# Display_PCB_Rev_1.net
KiCad netlist of a schematic drawn in EAGLE
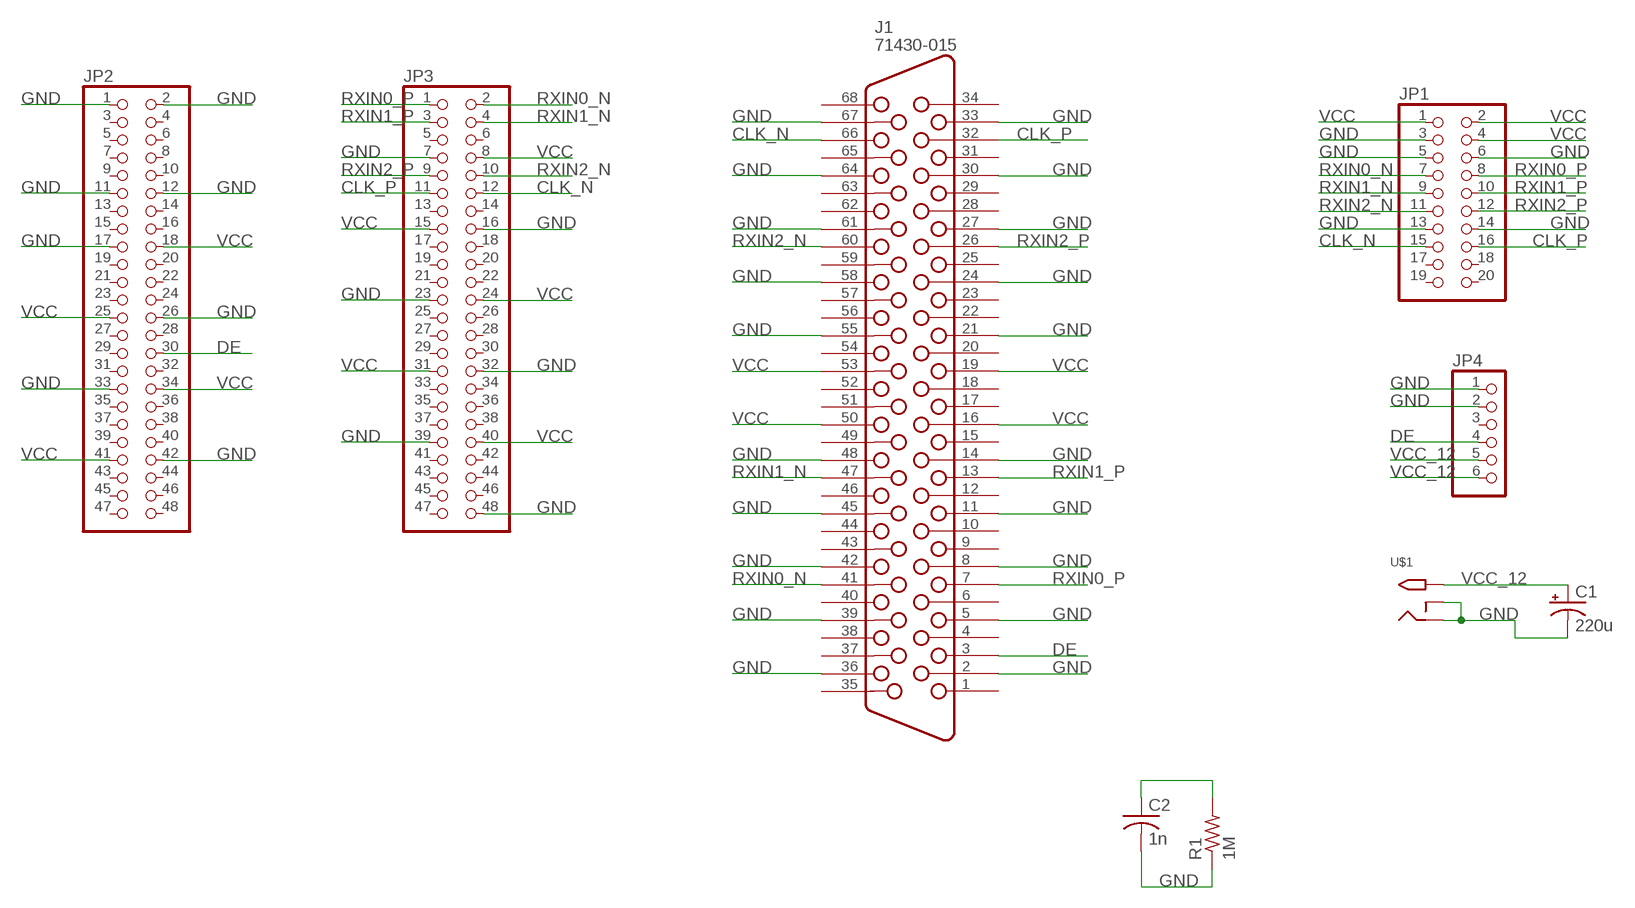
[diagram p0: schematic, sheet 1]

(export (version "E")
  (design (tool "Eeschema 10.0.6"))
  (components
    (comp (ref "C1")
      (value "220u")
      (footprint "eagle-import:E5-8,5")
      (libsource (lib "eagle-import") (part "CPOL-USE5-8.5"))
    )
    (comp (ref "C2")
      (value "1n")
      (footprint "eagle-import:C0805")
      (libsource (lib "eagle-import") (part "C-USC0805"))
    )
    (comp (ref "J1")
      (value "71430-015")
      (footprint "eagle-import:71430-015")
      (libsource (lib "eagle-import") (part "71430-015"))
    )
    (comp (ref "JP1")
      (value "PINHD-2X10M")
      (footprint "eagle-import:2X10M")
      (libsource (lib "eagle-import") (part "PINHD-2X10M"))
    )
    (comp (ref "JP2")
      (value "PINHD-2X24")
      (footprint "eagle-import:2X24")
      (libsource (lib "eagle-import") (part "PINHD-2X24"))
    )
    (comp (ref "JP3")
      (value "PINHD-2X24")
      (footprint "eagle-import:2X24")
      (libsource (lib "eagle-import") (part "PINHD-2X24"))
    )
    (comp (ref "JP4")
      (value "PINHD-1X6M")
      (footprint "eagle-import:1X06M")
      (libsource (lib "eagle-import") (part "PINHD-1X6M"))
    )
    (comp (ref "R1")
      (value "1M")
      (footprint "eagle-import:R0805W")
      (libsource (lib "eagle-import") (part "R-US_R0805W"))
    )
    (comp (ref "U$1")
      (value "2.1MMJACKTHM")
      (footprint "eagle-import:PJ-102A")
      (libsource (lib "eagle-import") (part "2.1MMJACKTHM"))
    )
  )
  (nets
    (net (code "1") (name "/CLK_N") (class "Default")
      (node (ref "J1") (pin "66") (pinfunction "66_66") (pintype "bidirectional"))
      (node (ref "JP1") (pin "15") (pinfunction "15_15") (pintype "passive"))
      (node (ref "JP3") (pin "12") (pinfunction "12_12") (pintype "passive"))
    )
    (net (code "2") (name "/CLK_P") (class "Default")
      (node (ref "J1") (pin "32") (pinfunction "32_32") (pintype "bidirectional"))
      (node (ref "JP1") (pin "16") (pinfunction "16_16") (pintype "passive"))
      (node (ref "JP3") (pin "11") (pinfunction "11_11") (pintype "passive"))
    )
    (net (code "3") (name "/DE") (class "Default")
      (node (ref "J1") (pin "3") (pinfunction "3_3") (pintype "bidirectional"))
      (node (ref "JP2") (pin "30") (pinfunction "30_30") (pintype "passive"))
      (node (ref "JP4") (pin "4") (pinfunction "4_4") (pintype "passive"))
    )
    (net (code "4") (name "/GND") (class "Default")
      (node (ref "C1") (pin "-") (pinfunction "-_-") (pintype "passive"))
      (node (ref "C2") (pin "2") (pinfunction "2_2") (pintype "passive"))
      (node (ref "J1") (pin "11") (pinfunction "11_11") (pintype "bidirectional"))
      (node (ref "J1") (pin "14") (pinfunction "14_14") (pintype "bidirectional"))
      (node (ref "J1") (pin "2") (pinfunction "2_2") (pintype "bidirectional"))
      (node (ref "J1") (pin "21") (pinfunction "21_21") (pintype "bidirectional"))
      (node (ref "J1") (pin "24") (pinfunction "24_24") (pintype "bidirectional"))
      (node (ref "J1") (pin "27") (pinfunction "27_27") (pintype "bidirectional"))
      (node (ref "J1") (pin "30") (pinfunction "30_30") (pintype "bidirectional"))
      (node (ref "J1") (pin "33") (pinfunction "33_33") (pintype "bidirectional"))
      (node (ref "J1") (pin "36") (pinfunction "36_36") (pintype "bidirectional"))
      (node (ref "J1") (pin "39") (pinfunction "39_39") (pintype "bidirectional"))
      (node (ref "J1") (pin "42") (pinfunction "42_42") (pintype "bidirectional"))
      (node (ref "J1") (pin "45") (pinfunction "45_45") (pintype "bidirectional"))
      (node (ref "J1") (pin "48") (pinfunction "48_48") (pintype "bidirectional"))
      (node (ref "J1") (pin "5") (pinfunction "5_5") (pintype "bidirectional"))
      (node (ref "J1") (pin "55") (pinfunction "55_55") (pintype "bidirectional"))
      (node (ref "J1") (pin "58") (pinfunction "58_58") (pintype "bidirectional"))
      (node (ref "J1") (pin "61") (pinfunction "61_61") (pintype "bidirectional"))
      (node (ref "J1") (pin "64") (pinfunction "64_64") (pintype "bidirectional"))
      (node (ref "J1") (pin "67") (pinfunction "67_67") (pintype "bidirectional"))
      (node (ref "J1") (pin "8") (pinfunction "8_8") (pintype "bidirectional"))
      (node (ref "JP1") (pin "13") (pinfunction "13_13") (pintype "passive"))
      (node (ref "JP1") (pin "14") (pinfunction "14_14") (pintype "passive"))
      (node (ref "JP1") (pin "3") (pinfunction "3_3") (pintype "passive"))
      (node (ref "JP1") (pin "5") (pinfunction "5_5") (pintype "passive"))
      (node (ref "JP1") (pin "6") (pinfunction "6_6") (pintype "passive"))
      (node (ref "JP2") (pin "1") (pinfunction "1_1") (pintype "passive"))
      (node (ref "JP2") (pin "11") (pinfunction "11_11") (pintype "passive"))
      (node (ref "JP2") (pin "12") (pinfunction "12_12") (pintype "passive"))
      (node (ref "JP2") (pin "17") (pinfunction "17_17") (pintype "passive"))
      (node (ref "JP2") (pin "2") (pinfunction "2_2") (pintype "passive"))
      (node (ref "JP2") (pin "26") (pinfunction "26_26") (pintype "passive"))
      (node (ref "JP2") (pin "33") (pinfunction "33_33") (pintype "passive"))
      (node (ref "JP2") (pin "42") (pinfunction "42_42") (pintype "passive"))
      (node (ref "JP3") (pin "16") (pinfunction "16_16") (pintype "passive"))
      (node (ref "JP3") (pin "23") (pinfunction "23_23") (pintype "passive"))
      (node (ref "JP3") (pin "32") (pinfunction "32_32") (pintype "passive"))
      (node (ref "JP3") (pin "39") (pinfunction "39_39") (pintype "passive"))
      (node (ref "JP3") (pin "48") (pinfunction "48_48") (pintype "passive"))
      (node (ref "JP3") (pin "7") (pinfunction "7_7") (pintype "passive"))
      (node (ref "JP4") (pin "1") (pinfunction "1_1") (pintype "passive"))
      (node (ref "JP4") (pin "2") (pinfunction "2_2") (pintype "passive"))
      (node (ref "R1") (pin "1") (pinfunction "1_1") (pintype "passive"))
      (node (ref "U$1") (pin "RING") (pinfunction "RING_RING") (pintype "bidirectional"))
      (node (ref "U$1") (pin "RING_SW") (pinfunction "RING_SW_RING_SW") (pintype "bidirectional"))
    )
    (net (code "5") (name "/RXIN0_N") (class "Default")
      (node (ref "J1") (pin "41") (pinfunction "41_41") (pintype "bidirectional"))
      (node (ref "JP1") (pin "7") (pinfunction "7_7") (pintype "passive"))
      (node (ref "JP3") (pin "2") (pinfunction "2_2") (pintype "passive"))
    )
    (net (code "6") (name "/RXIN0_P") (class "Default")
      (node (ref "J1") (pin "7") (pinfunction "7_7") (pintype "bidirectional"))
      (node (ref "JP1") (pin "8") (pinfunction "8_8") (pintype "passive"))
      (node (ref "JP3") (pin "1") (pinfunction "1_1") (pintype "passive"))
    )
    (net (code "7") (name "/RXIN1_N") (class "Default")
      (node (ref "J1") (pin "47") (pinfunction "47_47") (pintype "bidirectional"))
      (node (ref "JP1") (pin "9") (pinfunction "9_9") (pintype "passive"))
      (node (ref "JP3") (pin "4") (pinfunction "4_4") (pintype "passive"))
    )
    (net (code "8") (name "/RXIN1_P") (class "Default")
      (node (ref "J1") (pin "13") (pinfunction "13_13") (pintype "bidirectional"))
      (node (ref "JP1") (pin "10") (pinfunction "10_10") (pintype "passive"))
      (node (ref "JP3") (pin "3") (pinfunction "3_3") (pintype "passive"))
    )
    (net (code "9") (name "/RXIN2_N") (class "Default")
      (node (ref "J1") (pin "60") (pinfunction "60_60") (pintype "bidirectional"))
      (node (ref "JP1") (pin "11") (pinfunction "11_11") (pintype "passive"))
      (node (ref "JP3") (pin "10") (pinfunction "10_10") (pintype "passive"))
    )
    (net (code "10") (name "/RXIN2_P") (class "Default")
      (node (ref "J1") (pin "26") (pinfunction "26_26") (pintype "bidirectional"))
      (node (ref "JP1") (pin "12") (pinfunction "12_12") (pintype "passive"))
      (node (ref "JP3") (pin "9") (pinfunction "9_9") (pintype "passive"))
    )
    (net (code "11") (name "/VCC") (class "Default")
      (node (ref "J1") (pin "16") (pinfunction "16_16") (pintype "bidirectional"))
      (node (ref "J1") (pin "19") (pinfunction "19_19") (pintype "bidirectional"))
      (node (ref "J1") (pin "50") (pinfunction "50_50") (pintype "bidirectional"))
      (node (ref "J1") (pin "53") (pinfunction "53_53") (pintype "bidirectional"))
      (node (ref "JP1") (pin "1") (pinfunction "1_1") (pintype "passive"))
      (node (ref "JP1") (pin "2") (pinfunction "2_2") (pintype "passive"))
      (node (ref "JP1") (pin "4") (pinfunction "4_4") (pintype "passive"))
      (node (ref "JP2") (pin "18") (pinfunction "18_18") (pintype "passive"))
      (node (ref "JP2") (pin "25") (pinfunction "25_25") (pintype "passive"))
      (node (ref "JP2") (pin "34") (pinfunction "34_34") (pintype "passive"))
      (node (ref "JP2") (pin "41") (pinfunction "41_41") (pintype "passive"))
      (node (ref "JP3") (pin "15") (pinfunction "15_15") (pintype "passive"))
      (node (ref "JP3") (pin "24") (pinfunction "24_24") (pintype "passive"))
      (node (ref "JP3") (pin "31") (pinfunction "31_31") (pintype "passive"))
      (node (ref "JP3") (pin "40") (pinfunction "40_40") (pintype "passive"))
      (node (ref "JP3") (pin "8") (pinfunction "8_8") (pintype "passive"))
    )
    (net (code "12") (name "/VCC_12") (class "Default")
      (node (ref "C1") (pin "+") (pinfunction "+_+") (pintype "passive"))
      (node (ref "JP4") (pin "5") (pinfunction "5_5") (pintype "passive"))
      (node (ref "JP4") (pin "6") (pinfunction "6_6") (pintype "passive"))
      (node (ref "U$1") (pin "TIP") (pinfunction "TIP_TIP") (pintype "bidirectional"))
    )
    (net (code "13") (name "Net-(C2-Pad1)") (class "Default")
      (node (ref "C2") (pin "1") (pinfunction "1_1") (pintype "passive"))
      (node (ref "R1") (pin "2") (pinfunction "2_2") (pintype "passive"))
    )
    (net (code "14") (name "unconnected-(J1-Pad1)") (class "Default")
      (node (ref "J1") (pin "1") (pinfunction "1_1") (pintype "bidirectional"))
    )
    (net (code "15") (name "unconnected-(J1-Pad4)") (class "Default")
      (node (ref "J1") (pin "4") (pinfunction "4_4") (pintype "bidirectional"))
    )
    (net (code "16") (name "unconnected-(J1-Pad6)") (class "Default")
      (node (ref "J1") (pin "6") (pinfunction "6_6") (pintype "bidirectional"))
    )
    (net (code "17") (name "unconnected-(J1-Pad9)") (class "Default")
      (node (ref "J1") (pin "9") (pinfunction "9_9") (pintype "bidirectional"))
    )
    (net (code "18") (name "unconnected-(J1-Pad10)") (class "Default")
      (node (ref "J1") (pin "10") (pinfunction "10_10") (pintype "bidirectional"))
    )
    (net (code "19") (name "unconnected-(J1-Pad12)") (class "Default")
      (node (ref "J1") (pin "12") (pinfunction "12_12") (pintype "bidirectional"))
    )
    (net (code "20") (name "unconnected-(J1-Pad15)") (class "Default")
      (node (ref "J1") (pin "15") (pinfunction "15_15") (pintype "bidirectional"))
    )
    (net (code "21") (name "unconnected-(J1-Pad17)") (class "Default")
      (node (ref "J1") (pin "17") (pinfunction "17_17") (pintype "bidirectional"))
    )
    (net (code "22") (name "unconnected-(J1-Pad18)") (class "Default")
      (node (ref "J1") (pin "18") (pinfunction "18_18") (pintype "bidirectional"))
    )
    (net (code "23") (name "unconnected-(J1-Pad20)") (class "Default")
      (node (ref "J1") (pin "20") (pinfunction "20_20") (pintype "bidirectional"))
    )
    (net (code "24") (name "unconnected-(J1-Pad22)") (class "Default")
      (node (ref "J1") (pin "22") (pinfunction "22_22") (pintype "bidirectional"))
    )
    (net (code "25") (name "unconnected-(J1-Pad23)") (class "Default")
      (node (ref "J1") (pin "23") (pinfunction "23_23") (pintype "bidirectional"))
    )
    (net (code "26") (name "unconnected-(J1-Pad25)") (class "Default")
      (node (ref "J1") (pin "25") (pinfunction "25_25") (pintype "bidirectional"))
    )
    (net (code "27") (name "unconnected-(J1-Pad28)") (class "Default")
      (node (ref "J1") (pin "28") (pinfunction "28_28") (pintype "bidirectional"))
    )
    (net (code "28") (name "unconnected-(J1-Pad29)") (class "Default")
      (node (ref "J1") (pin "29") (pinfunction "29_29") (pintype "bidirectional"))
    )
    (net (code "29") (name "unconnected-(J1-Pad31)") (class "Default")
      (node (ref "J1") (pin "31") (pinfunction "31_31") (pintype "bidirectional"))
    )
    (net (code "30") (name "unconnected-(J1-Pad34)") (class "Default")
      (node (ref "J1") (pin "34") (pinfunction "34_34") (pintype "bidirectional"))
    )
    (net (code "31") (name "unconnected-(J1-Pad35)") (class "Default")
      (node (ref "J1") (pin "35") (pinfunction "35_35") (pintype "bidirectional"))
    )
    (net (code "32") (name "unconnected-(J1-Pad37)") (class "Default")
      (node (ref "J1") (pin "37") (pinfunction "37_37") (pintype "bidirectional"))
    )
    (net (code "33") (name "unconnected-(J1-Pad38)") (class "Default")
      (node (ref "J1") (pin "38") (pinfunction "38_38") (pintype "bidirectional"))
    )
    (net (code "34") (name "unconnected-(J1-Pad40)") (class "Default")
      (node (ref "J1") (pin "40") (pinfunction "40_40") (pintype "bidirectional"))
    )
    (net (code "35") (name "unconnected-(J1-Pad43)") (class "Default")
      (node (ref "J1") (pin "43") (pinfunction "43_43") (pintype "bidirectional"))
    )
    (net (code "36") (name "unconnected-(J1-Pad44)") (class "Default")
      (node (ref "J1") (pin "44") (pinfunction "44_44") (pintype "bidirectional"))
    )
    (net (code "37") (name "unconnected-(J1-Pad46)") (class "Default")
      (node (ref "J1") (pin "46") (pinfunction "46_46") (pintype "bidirectional"))
    )
    (net (code "38") (name "unconnected-(J1-Pad49)") (class "Default")
      (node (ref "J1") (pin "49") (pinfunction "49_49") (pintype "bidirectional"))
    )
    (net (code "39") (name "unconnected-(J1-Pad51)") (class "Default")
      (node (ref "J1") (pin "51") (pinfunction "51_51") (pintype "bidirectional"))
    )
    (net (code "40") (name "unconnected-(J1-Pad52)") (class "Default")
      (node (ref "J1") (pin "52") (pinfunction "52_52") (pintype "bidirectional"))
    )
    (net (code "41") (name "unconnected-(J1-Pad54)") (class "Default")
      (node (ref "J1") (pin "54") (pinfunction "54_54") (pintype "bidirectional"))
    )
    (net (code "42") (name "unconnected-(J1-Pad56)") (class "Default")
      (node (ref "J1") (pin "56") (pinfunction "56_56") (pintype "bidirectional"))
    )
    (net (code "43") (name "unconnected-(J1-Pad57)") (class "Default")
      (node (ref "J1") (pin "57") (pinfunction "57_57") (pintype "bidirectional"))
    )
    (net (code "44") (name "unconnected-(J1-Pad59)") (class "Default")
      (node (ref "J1") (pin "59") (pinfunction "59_59") (pintype "bidirectional"))
    )
    (net (code "45") (name "unconnected-(J1-Pad62)") (class "Default")
      (node (ref "J1") (pin "62") (pinfunction "62_62") (pintype "bidirectional"))
    )
    (net (code "46") (name "unconnected-(J1-Pad63)") (class "Default")
      (node (ref "J1") (pin "63") (pinfunction "63_63") (pintype "bidirectional"))
    )
    (net (code "47") (name "unconnected-(J1-Pad65)") (class "Default")
      (node (ref "J1") (pin "65") (pinfunction "65_65") (pintype "bidirectional"))
    )
    (net (code "48") (name "unconnected-(J1-Pad68)") (class "Default")
      (node (ref "J1") (pin "68") (pinfunction "68_68") (pintype "bidirectional"))
    )
    (net (code "49") (name "unconnected-(JP1-Pad17)") (class "Default")
      (node (ref "JP1") (pin "17") (pinfunction "17_17") (pintype "passive"))
    )
    (net (code "50") (name "unconnected-(JP1-Pad18)") (class "Default")
      (node (ref "JP1") (pin "18") (pinfunction "18_18") (pintype "passive"))
    )
    (net (code "51") (name "unconnected-(JP1-Pad19)") (class "Default")
      (node (ref "JP1") (pin "19") (pinfunction "19_19") (pintype "passive"))
    )
    (net (code "52") (name "unconnected-(JP1-Pad20)") (class "Default")
      (node (ref "JP1") (pin "20") (pinfunction "20_20") (pintype "passive"))
    )
    (net (code "53") (name "unconnected-(JP2-Pad3)") (class "Default")
      (node (ref "JP2") (pin "3") (pinfunction "3_3") (pintype "passive"))
    )
    (net (code "54") (name "unconnected-(JP2-Pad4)") (class "Default")
      (node (ref "JP2") (pin "4") (pinfunction "4_4") (pintype "passive"))
    )
    (net (code "55") (name "unconnected-(JP2-Pad5)") (class "Default")
      (node (ref "JP2") (pin "5") (pinfunction "5_5") (pintype "passive"))
    )
    (net (code "56") (name "unconnected-(JP2-Pad6)") (class "Default")
      (node (ref "JP2") (pin "6") (pinfunction "6_6") (pintype "passive"))
    )
    (net (code "57") (name "unconnected-(JP2-Pad7)") (class "Default")
      (node (ref "JP2") (pin "7") (pinfunction "7_7") (pintype "passive"))
    )
    (net (code "58") (name "unconnected-(JP2-Pad8)") (class "Default")
      (node (ref "JP2") (pin "8") (pinfunction "8_8") (pintype "passive"))
    )
    (net (code "59") (name "unconnected-(JP2-Pad9)") (class "Default")
      (node (ref "JP2") (pin "9") (pinfunction "9_9") (pintype "passive"))
    )
    (net (code "60") (name "unconnected-(JP2-Pad10)") (class "Default")
      (node (ref "JP2") (pin "10") (pinfunction "10_10") (pintype "passive"))
    )
    (net (code "61") (name "unconnected-(JP2-Pad13)") (class "Default")
      (node (ref "JP2") (pin "13") (pinfunction "13_13") (pintype "passive"))
    )
    (net (code "62") (name "unconnected-(JP2-Pad14)") (class "Default")
      (node (ref "JP2") (pin "14") (pinfunction "14_14") (pintype "passive"))
    )
    (net (code "63") (name "unconnected-(JP2-Pad15)") (class "Default")
      (node (ref "JP2") (pin "15") (pinfunction "15_15") (pintype "passive"))
    )
    (net (code "64") (name "unconnected-(JP2-Pad16)") (class "Default")
      (node (ref "JP2") (pin "16") (pinfunction "16_16") (pintype "passive"))
    )
    (net (code "65") (name "unconnected-(JP2-Pad19)") (class "Default")
      (node (ref "JP2") (pin "19") (pinfunction "19_19") (pintype "passive"))
    )
    (net (code "66") (name "unconnected-(JP2-Pad20)") (class "Default")
      (node (ref "JP2") (pin "20") (pinfunction "20_20") (pintype "passive"))
    )
    (net (code "67") (name "unconnected-(JP2-Pad21)") (class "Default")
      (node (ref "JP2") (pin "21") (pinfunction "21_21") (pintype "passive"))
    )
    (net (code "68") (name "unconnected-(JP2-Pad22)") (class "Default")
      (node (ref "JP2") (pin "22") (pinfunction "22_22") (pintype "passive"))
    )
    (net (code "69") (name "unconnected-(JP2-Pad23)") (class "Default")
      (node (ref "JP2") (pin "23") (pinfunction "23_23") (pintype "passive"))
    )
    (net (code "70") (name "unconnected-(JP2-Pad24)") (class "Default")
      (node (ref "JP2") (pin "24") (pinfunction "24_24") (pintype "passive"))
    )
    (net (code "71") (name "unconnected-(JP2-Pad27)") (class "Default")
      (node (ref "JP2") (pin "27") (pinfunction "27_27") (pintype "passive"))
    )
    (net (code "72") (name "unconnected-(JP2-Pad28)") (class "Default")
      (node (ref "JP2") (pin "28") (pinfunction "28_28") (pintype "passive"))
    )
    (net (code "73") (name "unconnected-(JP2-Pad29)") (class "Default")
      (node (ref "JP2") (pin "29") (pinfunction "29_29") (pintype "passive"))
    )
    (net (code "74") (name "unconnected-(JP2-Pad31)") (class "Default")
      (node (ref "JP2") (pin "31") (pinfunction "31_31") (pintype "passive"))
    )
    (net (code "75") (name "unconnected-(JP2-Pad32)") (class "Default")
      (node (ref "JP2") (pin "32") (pinfunction "32_32") (pintype "passive"))
    )
    (net (code "76") (name "unconnected-(JP2-Pad35)") (class "Default")
      (node (ref "JP2") (pin "35") (pinfunction "35_35") (pintype "passive"))
    )
    (net (code "77") (name "unconnected-(JP2-Pad36)") (class "Default")
      (node (ref "JP2") (pin "36") (pinfunction "36_36") (pintype "passive"))
    )
    (net (code "78") (name "unconnected-(JP2-Pad37)") (class "Default")
      (node (ref "JP2") (pin "37") (pinfunction "37_37") (pintype "passive"))
    )
    (net (code "79") (name "unconnected-(JP2-Pad38)") (class "Default")
      (node (ref "JP2") (pin "38") (pinfunction "38_38") (pintype "passive"))
    )
    (net (code "80") (name "unconnected-(JP2-Pad39)") (class "Default")
      (node (ref "JP2") (pin "39") (pinfunction "39_39") (pintype "passive"))
    )
    (net (code "81") (name "unconnected-(JP2-Pad40)") (class "Default")
      (node (ref "JP2") (pin "40") (pinfunction "40_40") (pintype "passive"))
    )
    (net (code "82") (name "unconnected-(JP2-Pad43)") (class "Default")
      (node (ref "JP2") (pin "43") (pinfunction "43_43") (pintype "passive"))
    )
    (net (code "83") (name "unconnected-(JP2-Pad44)") (class "Default")
      (node (ref "JP2") (pin "44") (pinfunction "44_44") (pintype "passive"))
    )
    (net (code "84") (name "unconnected-(JP2-Pad45)") (class "Default")
      (node (ref "JP2") (pin "45") (pinfunction "45_45") (pintype "passive"))
    )
    (net (code "85") (name "unconnected-(JP2-Pad46)") (class "Default")
      (node (ref "JP2") (pin "46") (pinfunction "46_46") (pintype "passive"))
    )
    (net (code "86") (name "unconnected-(JP2-Pad47)") (class "Default")
      (node (ref "JP2") (pin "47") (pinfunction "47_47") (pintype "passive"))
    )
    (net (code "87") (name "unconnected-(JP2-Pad48)") (class "Default")
      (node (ref "JP2") (pin "48") (pinfunction "48_48") (pintype "passive"))
    )
    (net (code "88") (name "unconnected-(JP3-Pad5)") (class "Default")
      (node (ref "JP3") (pin "5") (pinfunction "5_5") (pintype "passive"))
    )
    (net (code "89") (name "unconnected-(JP3-Pad6)") (class "Default")
      (node (ref "JP3") (pin "6") (pinfunction "6_6") (pintype "passive"))
    )
    (net (code "90") (name "unconnected-(JP3-Pad13)") (class "Default")
      (node (ref "JP3") (pin "13") (pinfunction "13_13") (pintype "passive"))
    )
    (net (code "91") (name "unconnected-(JP3-Pad14)") (class "Default")
      (node (ref "JP3") (pin "14") (pinfunction "14_14") (pintype "passive"))
    )
    (net (code "92") (name "unconnected-(JP3-Pad17)") (class "Default")
      (node (ref "JP3") (pin "17") (pinfunction "17_17") (pintype "passive"))
    )
    (net (code "93") (name "unconnected-(JP3-Pad18)") (class "Default")
      (node (ref "JP3") (pin "18") (pinfunction "18_18") (pintype "passive"))
    )
    (net (code "94") (name "unconnected-(JP3-Pad19)") (class "Default")
      (node (ref "JP3") (pin "19") (pinfunction "19_19") (pintype "passive"))
    )
    (net (code "95") (name "unconnected-(JP3-Pad20)") (class "Default")
      (node (ref "JP3") (pin "20") (pinfunction "20_20") (pintype "passive"))
    )
    (net (code "96") (name "unconnected-(JP3-Pad21)") (class "Default")
      (node (ref "JP3") (pin "21") (pinfunction "21_21") (pintype "passive"))
    )
    (net (code "97") (name "unconnected-(JP3-Pad22)") (class "Default")
      (node (ref "JP3") (pin "22") (pinfunction "22_22") (pintype "passive"))
    )
    (net (code "98") (name "unconnected-(JP3-Pad25)") (class "Default")
      (node (ref "JP3") (pin "25") (pinfunction "25_25") (pintype "passive"))
    )
    (net (code "99") (name "unconnected-(JP3-Pad26)") (class "Default")
      (node (ref "JP3") (pin "26") (pinfunction "26_26") (pintype "passive"))
    )
    (net (code "100") (name "unconnected-(JP3-Pad27)") (class "Default")
      (node (ref "JP3") (pin "27") (pinfunction "27_27") (pintype "passive"))
    )
    (net (code "101") (name "unconnected-(JP3-Pad28)") (class "Default")
      (node (ref "JP3") (pin "28") (pinfunction "28_28") (pintype "passive"))
    )
    (net (code "102") (name "unconnected-(JP3-Pad29)") (class "Default")
      (node (ref "JP3") (pin "29") (pinfunction "29_29") (pintype "passive"))
    )
    (net (code "103") (name "unconnected-(JP3-Pad30)") (class "Default")
      (node (ref "JP3") (pin "30") (pinfunction "30_30") (pintype "passive"))
    )
    (net (code "104") (name "unconnected-(JP3-Pad33)") (class "Default")
      (node (ref "JP3") (pin "33") (pinfunction "33_33") (pintype "passive"))
    )
    (net (code "105") (name "unconnected-(JP3-Pad34)") (class "Default")
      (node (ref "JP3") (pin "34") (pinfunction "34_34") (pintype "passive"))
    )
    (net (code "106") (name "unconnected-(JP3-Pad35)") (class "Default")
      (node (ref "JP3") (pin "35") (pinfunction "35_35") (pintype "passive"))
    )
    (net (code "107") (name "unconnected-(JP3-Pad36)") (class "Default")
      (node (ref "JP3") (pin "36") (pinfunction "36_36") (pintype "passive"))
    )
    (net (code "108") (name "unconnected-(JP3-Pad37)") (class "Default")
      (node (ref "JP3") (pin "37") (pinfunction "37_37") (pintype "passive"))
    )
    (net (code "109") (name "unconnected-(JP3-Pad38)") (class "Default")
      (node (ref "JP3") (pin "38") (pinfunction "38_38") (pintype "passive"))
    )
    (net (code "110") (name "unconnected-(JP3-Pad41)") (class "Default")
      (node (ref "JP3") (pin "41") (pinfunction "41_41") (pintype "passive"))
    )
    (net (code "111") (name "unconnected-(JP3-Pad42)") (class "Default")
      (node (ref "JP3") (pin "42") (pinfunction "42_42") (pintype "passive"))
    )
    (net (code "112") (name "unconnected-(JP3-Pad43)") (class "Default")
      (node (ref "JP3") (pin "43") (pinfunction "43_43") (pintype "passive"))
    )
    (net (code "113") (name "unconnected-(JP3-Pad44)") (class "Default")
      (node (ref "JP3") (pin "44") (pinfunction "44_44") (pintype "passive"))
    )
    (net (code "114") (name "unconnected-(JP3-Pad45)") (class "Default")
      (node (ref "JP3") (pin "45") (pinfunction "45_45") (pintype "passive"))
    )
    (net (code "115") (name "unconnected-(JP3-Pad46)") (class "Default")
      (node (ref "JP3") (pin "46") (pinfunction "46_46") (pintype "passive"))
    )
    (net (code "116") (name "unconnected-(JP3-Pad47)") (class "Default")
      (node (ref "JP3") (pin "47") (pinfunction "47_47") (pintype "passive"))
    )
    (net (code "117") (name "unconnected-(JP4-Pad3)") (class "Default")
      (node (ref "JP4") (pin "3") (pinfunction "3_3") (pintype "passive"))
    )
  )
)
